# Sheet1.net
KiCad netlist of a schematic drawn in Altium Designer
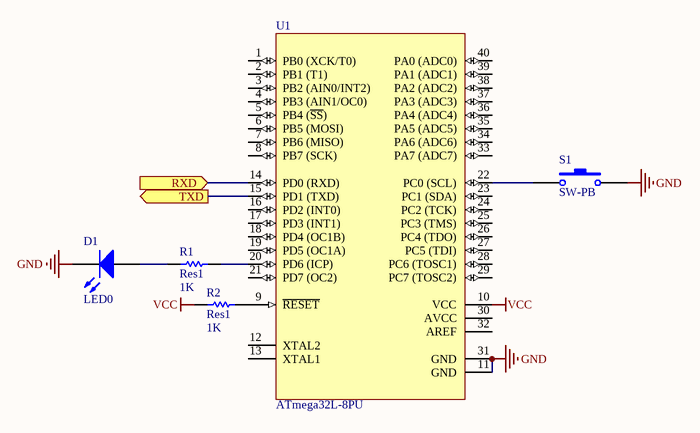
[diagram p0: Sheet1.SchDoc]

(export (version "E")
  (design (tool "Eeschema 10.0.6"))
  (components
    (comp (ref "D1")
      (value "LED0")
      (footprint "LED-0")
      (description "Typical INFRARED GaAs LED")
      (fields (field (name "PUBLISHER") "Altium Limited"))
      (libsource (lib "Miscellaneous Devices") (part "LED0"))
    )
    (comp (ref "R1")
      (value "Res1")
      (footprint "AXIAL-0.3")
      (description "Resistor")
      (fields (field (name "ALTIUM_VALUE") "1K") (field (name "PUBLISHER") "Altium Limited"))
      (libsource (lib "Miscellaneous Devices") (part "Res1"))
    )
    (comp (ref "R2")
      (value "Res1")
      (footprint "AXIAL-0.3")
      (description "Resistor")
      (fields (field (name "ALTIUM_VALUE") "1K") (field (name "PUBLISHER") "Altium Limited"))
      (libsource (lib "Miscellaneous Devices") (part "Res1"))
    )
    (comp (ref "S1")
      (value "SW-PB")
      (footprint "SPST-2")
      (description "Switch")
      (fields (field (name "PUBLISHER") "Altium Limited"))
      (libsource (lib "Miscellaneous Devices") (part "SW-PB"))
    )
    (comp (ref "U1")
      (value "ATmega32L-8PU")
      (footprint "40P6")
      (libsource (lib "Atmel Microcontroller megaAVR") (part "ATmega32L-8PU"))
    )
  )
  (nets
    (net (code "1") (name "/RXD") (class "Default")
      (node (ref "U1") (pin "14") (pinfunction "PD0_(RXD)_14") (pintype "bidirectional"))
    )
    (net (code "2") (name "/TXD") (class "Default")
      (node (ref "U1") (pin "15") (pinfunction "PD1_(TXD)_15") (pintype "bidirectional"))
    )
    (net (code "3") (name "GND") (class "Default")
      (node (ref "D1") (pin "2") (pinfunction "K_2") (pintype "passive"))
      (node (ref "S1") (pin "2") (pinfunction "2_2") (pintype "passive"))
      (node (ref "U1") (pin "11") (pinfunction "GND_11") (pintype "power_in"))
      (node (ref "U1") (pin "31") (pinfunction "GND_31") (pintype "power_in"))
    )
    (net (code "4") (name "Net-(D1-A)") (class "Default")
      (node (ref "D1") (pin "1") (pinfunction "A_1") (pintype "passive"))
      (node (ref "R1") (pin "2") (pinfunction "2_2") (pintype "passive"))
    )
    (net (code "5") (name "Net-(U1-PC0_(SCL))") (class "Default")
      (node (ref "S1") (pin "1") (pinfunction "1_1") (pintype "passive"))
      (node (ref "U1") (pin "22") (pinfunction "PC0_(SCL)_22") (pintype "bidirectional"))
    )
    (net (code "6") (name "Net-(U1-PD6_(ICP))") (class "Default")
      (node (ref "R1") (pin "1") (pinfunction "1_1") (pintype "passive"))
      (node (ref "U1") (pin "20") (pinfunction "PD6_(ICP)_20") (pintype "bidirectional"))
    )
    (net (code "7") (name "Net-(U1-~{RESET})") (class "Default")
      (node (ref "R2") (pin "2") (pinfunction "2_2") (pintype "passive"))
      (node (ref "U1") (pin "9") (pinfunction "~{RESET}_9") (pintype "input"))
    )
    (net (code "8") (name "VCC") (class "Default")
      (node (ref "R2") (pin "1") (pinfunction "1_1") (pintype "passive"))
      (node (ref "U1") (pin "10") (pinfunction "VCC_10") (pintype "power_in"))
    )
    (net (code "9") (name "unconnected-(U1-AREF-Pad32)") (class "Default")
      (node (ref "U1") (pin "32") (pinfunction "AREF_32") (pintype "passive"))
    )
    (net (code "10") (name "unconnected-(U1-AVCC-Pad30)") (class "Default")
      (node (ref "U1") (pin "30") (pinfunction "AVCC_30") (pintype "power_in"))
    )
    (net (code "11") (name "unconnected-(U1-PA0_(ADC0)-Pad40)") (class "Default")
      (node (ref "U1") (pin "40") (pinfunction "PA0_(ADC0)_40") (pintype "bidirectional"))
    )
    (net (code "12") (name "unconnected-(U1-PA1_(ADC1)-Pad39)") (class "Default")
      (node (ref "U1") (pin "39") (pinfunction "PA1_(ADC1)_39") (pintype "bidirectional"))
    )
    (net (code "13") (name "unconnected-(U1-PA2_(ADC2)-Pad38)") (class "Default")
      (node (ref "U1") (pin "38") (pinfunction "PA2_(ADC2)_38") (pintype "bidirectional"))
    )
    (net (code "14") (name "unconnected-(U1-PA3_(ADC3)-Pad37)") (class "Default")
      (node (ref "U1") (pin "37") (pinfunction "PA3_(ADC3)_37") (pintype "bidirectional"))
    )
    (net (code "15") (name "unconnected-(U1-PA4_(ADC4)-Pad36)") (class "Default")
      (node (ref "U1") (pin "36") (pinfunction "PA4_(ADC4)_36") (pintype "bidirectional"))
    )
    (net (code "16") (name "unconnected-(U1-PA5_(ADC5)-Pad35)") (class "Default")
      (node (ref "U1") (pin "35") (pinfunction "PA5_(ADC5)_35") (pintype "bidirectional"))
    )
    (net (code "17") (name "unconnected-(U1-PA6_(ADC6)-Pad34)") (class "Default")
      (node (ref "U1") (pin "34") (pinfunction "PA6_(ADC6)_34") (pintype "bidirectional"))
    )
    (net (code "18") (name "unconnected-(U1-PA7_(ADC7)-Pad33)") (class "Default")
      (node (ref "U1") (pin "33") (pinfunction "PA7_(ADC7)_33") (pintype "bidirectional"))
    )
    (net (code "19") (name "unconnected-(U1-PB0_(XCK{slash}T0)-Pad1)") (class "Default")
      (node (ref "U1") (pin "1") (pinfunction "PB0_(XCK/T0)_1") (pintype "bidirectional"))
    )
    (net (code "20") (name "unconnected-(U1-PB1_(T1)-Pad2)") (class "Default")
      (node (ref "U1") (pin "2") (pinfunction "PB1_(T1)_2") (pintype "bidirectional"))
    )
    (net (code "21") (name "unconnected-(U1-PB2_(AIN0{slash}INT2)-Pad3)") (class "Default")
      (node (ref "U1") (pin "3") (pinfunction "PB2_(AIN0/INT2)_3") (pintype "bidirectional"))
    )
    (net (code "22") (name "unconnected-(U1-PB3_(AIN1{slash}OC0)-Pad4)") (class "Default")
      (node (ref "U1") (pin "4") (pinfunction "PB3_(AIN1/OC0)_4") (pintype "bidirectional"))
    )
    (net (code "23") (name "unconnected-(U1-PB4_(~{SS})-Pad5)") (class "Default")
      (node (ref "U1") (pin "5") (pinfunction "PB4_(~{SS})_5") (pintype "bidirectional"))
    )
    (net (code "24") (name "unconnected-(U1-PB5_(MOSI)-Pad6)") (class "Default")
      (node (ref "U1") (pin "6") (pinfunction "PB5_(MOSI)_6") (pintype "bidirectional"))
    )
    (net (code "25") (name "unconnected-(U1-PB6_(MISO)-Pad7)") (class "Default")
      (node (ref "U1") (pin "7") (pinfunction "PB6_(MISO)_7") (pintype "bidirectional"))
    )
    (net (code "26") (name "unconnected-(U1-PB7_(SCK)-Pad8)") (class "Default")
      (node (ref "U1") (pin "8") (pinfunction "PB7_(SCK)_8") (pintype "bidirectional"))
    )
    (net (code "27") (name "unconnected-(U1-PC1_(SDA)-Pad23)") (class "Default")
      (node (ref "U1") (pin "23") (pinfunction "PC1_(SDA)_23") (pintype "bidirectional"))
    )
    (net (code "28") (name "unconnected-(U1-PC2_(TCK)-Pad24)") (class "Default")
      (node (ref "U1") (pin "24") (pinfunction "PC2_(TCK)_24") (pintype "bidirectional"))
    )
    (net (code "29") (name "unconnected-(U1-PC3_(TMS)-Pad25)") (class "Default")
      (node (ref "U1") (pin "25") (pinfunction "PC3_(TMS)_25") (pintype "bidirectional"))
    )
    (net (code "30") (name "unconnected-(U1-PC4_(TDO)-Pad26)") (class "Default")
      (node (ref "U1") (pin "26") (pinfunction "PC4_(TDO)_26") (pintype "bidirectional"))
    )
    (net (code "31") (name "unconnected-(U1-PC5_(TDI)-Pad27)") (class "Default")
      (node (ref "U1") (pin "27") (pinfunction "PC5_(TDI)_27") (pintype "bidirectional"))
    )
    (net (code "32") (name "unconnected-(U1-PC6_(TOSC1)-Pad28)") (class "Default")
      (node (ref "U1") (pin "28") (pinfunction "PC6_(TOSC1)_28") (pintype "bidirectional"))
    )
    (net (code "33") (name "unconnected-(U1-PC7_(TOSC2)-Pad29)") (class "Default")
      (node (ref "U1") (pin "29") (pinfunction "PC7_(TOSC2)_29") (pintype "bidirectional"))
    )
    (net (code "34") (name "unconnected-(U1-PD2_(INT0)-Pad16)") (class "Default")
      (node (ref "U1") (pin "16") (pinfunction "PD2_(INT0)_16") (pintype "bidirectional"))
    )
    (net (code "35") (name "unconnected-(U1-PD3_(INT1)-Pad17)") (class "Default")
      (node (ref "U1") (pin "17") (pinfunction "PD3_(INT1)_17") (pintype "bidirectional"))
    )
    (net (code "36") (name "unconnected-(U1-PD4_(OC1B)-Pad18)") (class "Default")
      (node (ref "U1") (pin "18") (pinfunction "PD4_(OC1B)_18") (pintype "bidirectional"))
    )
    (net (code "37") (name "unconnected-(U1-PD5_(OC1A)-Pad19)") (class "Default")
      (node (ref "U1") (pin "19") (pinfunction "PD5_(OC1A)_19") (pintype "bidirectional"))
    )
    (net (code "38") (name "unconnected-(U1-PD7_(OC2)-Pad21)") (class "Default")
      (node (ref "U1") (pin "21") (pinfunction "PD7_(OC2)_21") (pintype "bidirectional"))
    )
    (net (code "39") (name "unconnected-(U1-XTAL1-Pad13)") (class "Default")
      (node (ref "U1") (pin "13") (pinfunction "XTAL1_13") (pintype "passive"))
    )
    (net (code "40") (name "unconnected-(U1-XTAL2-Pad12)") (class "Default")
      (node (ref "U1") (pin "12") (pinfunction "XTAL2_12") (pintype "passive"))
    )
  )
)
